# Cap_Drop_LDR.net
KiCad netlist of a schematic drawn in EAGLE
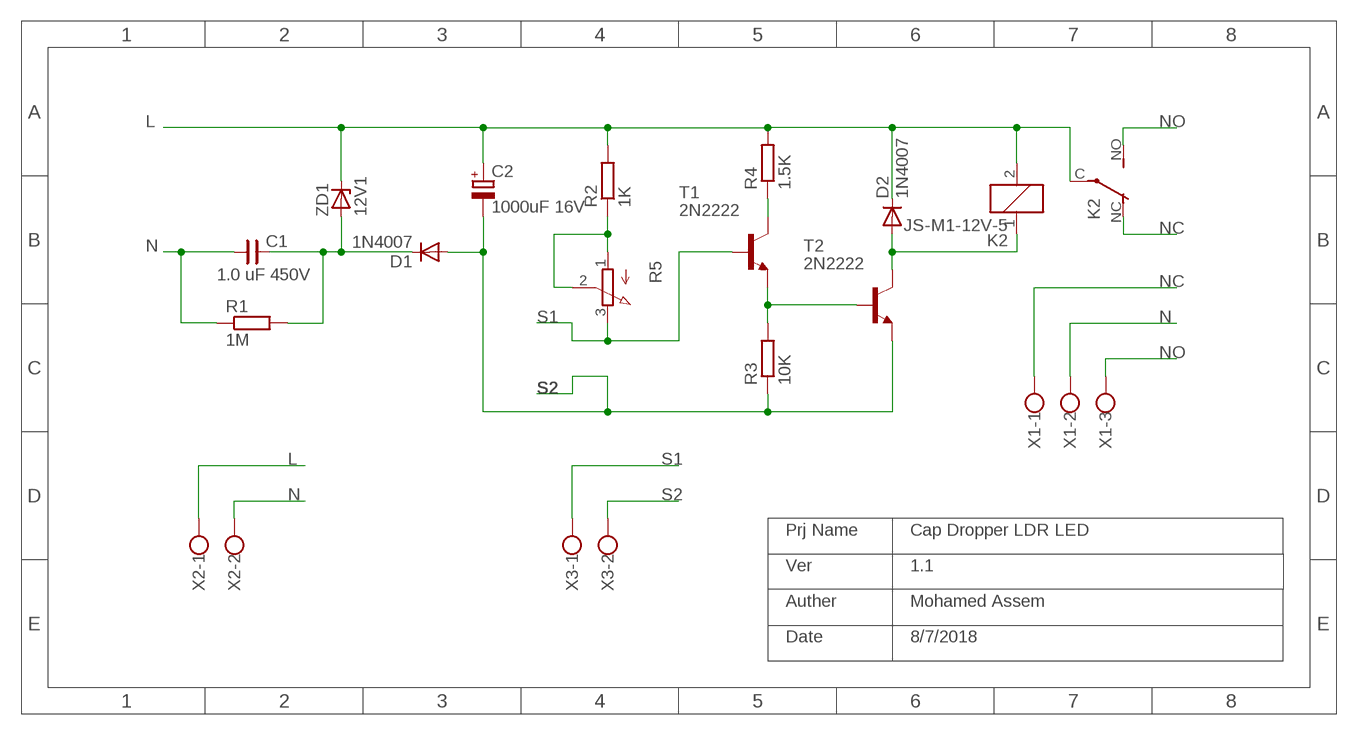
[diagram p0: schematic, sheet 1]

(export (version "E")
  (design (tool "Eeschema 10.0.6"))
  (components
    (comp (ref "C1")
      (value "1.0 uF 450V")
      (footprint "eagle-import:C150-190X070")
      (libsource (lib "eagle-import") (part "CNP-C150-190X070"))
    )
    (comp (ref "C2")
      (value "1000uF 16V")
      (footprint "eagle-import:E5-8,5")
      (libsource (lib "eagle-import") (part "CPOL-EUE5-8.5"))
    )
    (comp (ref "D1")
      (value "1N4007")
      (footprint "eagle-import:DO41-10")
      (libsource (lib "eagle-import") (part "1N4004"))
    )
    (comp (ref "D2")
      (value "1N4007")
      (footprint "eagle-import:DO41-10")
      (libsource (lib "eagle-import") (part "1N4004"))
    )
    (comp (ref "K2")
      (value "JS-M1-12V-5")
      (footprint "eagle-import:JS-M")
      (fields (field (name "MF") "FARNELL") (field (name "MPN") "JSM1-12V-5"))
      (libsource (lib "eagle-import") (part "JS-M1-12V-5"))
    )
    (comp (ref "R1")
      (value "1M")
      (footprint "eagle-import:0207_10")
      (libsource (lib "eagle-import") (part "R-EU_0207/10"))
    )
    (comp (ref "R2")
      (value "1K")
      (footprint "eagle-import:0207_10")
      (libsource (lib "eagle-import") (part "R-EU_0207/10"))
    )
    (comp (ref "R3")
      (value "10K")
      (footprint "eagle-import:0207_10")
      (libsource (lib "eagle-import") (part "R-EU_0207/10"))
    )
    (comp (ref "R4")
      (value "1.5K")
      (footprint "eagle-import:0207_10")
      (libsource (lib "eagle-import") (part "R-EU_0207/10"))
    )
    (comp (ref "R5")
      (value "3RP/1610N")
      (footprint "eagle-import:3RP_1610N")
      (libsource (lib "eagle-import") (part "3RP/1610N"))
    )
    (comp (ref "T1")
      (value "2N2222")
      (footprint "eagle-import:TO92-EBC-OVAL")
      (libsource (lib "eagle-import") (part "2N2222"))
    )
    (comp (ref "T2")
      (value "2N2222")
      (footprint "eagle-import:TO92-EBC-OVAL")
      (libsource (lib "eagle-import") (part "2N2222"))
    )
    (comp (ref "X1")
      (value "W237-103")
      (footprint "eagle-import:W237-103")
      (libsource (lib "eagle-import") (part "W237-103"))
    )
    (comp (ref "X2")
      (value "W237-102")
      (footprint "eagle-import:W237-102")
      (libsource (lib "eagle-import") (part "W237-102"))
    )
    (comp (ref "X3")
      (value "W237-102")
      (footprint "eagle-import:W237-102")
      (libsource (lib "eagle-import") (part "W237-102"))
    )
    (comp (ref "ZD1")
      (value "12V1")
      (footprint "eagle-import:DO35Z10")
      (libsource (lib "eagle-import") (part "ZD-DO35Z10"))
    )
  )
  (nets
    (net (code "1") (name "/L") (class "Default")
      (node (ref "C2") (pin "+") (pinfunction "+_+") (pintype "passive"))
      (node (ref "D2") (pin "C") (pinfunction "C_C") (pintype "passive"))
      (node (ref "K2") (pin "2") (pinfunction "2_2") (pintype "passive"))
      (node (ref "K2") (pin "C") (pinfunction "P_C") (pintype "passive"))
      (node (ref "R2") (pin "2") (pinfunction "2_2") (pintype "passive"))
      (node (ref "R4") (pin "2") (pinfunction "2_2") (pintype "passive"))
      (node (ref "X2") (pin "1") (pinfunction "KL_1") (pintype "passive"))
      (node (ref "ZD1") (pin "C") (pinfunction "C_C") (pintype "passive"))
    )
    (net (code "2") (name "/N") (class "Default")
      (node (ref "C1") (pin "1") (pinfunction "1_1") (pintype "passive"))
      (node (ref "R1") (pin "1") (pinfunction "1_1") (pintype "passive"))
      (node (ref "X1") (pin "2") (pinfunction "KL_2") (pintype "passive"))
      (node (ref "X2") (pin "2") (pinfunction "KL_2") (pintype "passive"))
    )
    (net (code "3") (name "/NC") (class "Default")
      (node (ref "K2") (pin "NC") (pinfunction "O_NC") (pintype "passive"))
      (node (ref "X1") (pin "1") (pinfunction "KL_1") (pintype "passive"))
    )
    (net (code "4") (name "/NO") (class "Default")
      (node (ref "K2") (pin "NO") (pinfunction "S_NO") (pintype "passive"))
      (node (ref "X1") (pin "3") (pinfunction "KL_3") (pintype "passive"))
    )
    (net (code "5") (name "/S1") (class "Default")
      (node (ref "R5") (pin "3") (pinfunction "E_3") (pintype "passive"))
      (node (ref "T1") (pin "B") (pinfunction "B_B") (pintype "passive"))
      (node (ref "X3") (pin "1") (pinfunction "KL_1") (pintype "passive"))
    )
    (net (code "6") (name "/S2") (class "Default")
      (node (ref "C2") (pin "-") (pinfunction "-_-") (pintype "passive"))
      (node (ref "D1") (pin "A") (pinfunction "A_A") (pintype "passive"))
      (node (ref "R3") (pin "1") (pinfunction "1_1") (pintype "passive"))
      (node (ref "T2") (pin "E") (pinfunction "E_E") (pintype "passive"))
      (node (ref "X3") (pin "2") (pinfunction "KL_2") (pintype "passive"))
    )
    (net (code "7") (name "Net-(C1-Pad2)") (class "Default")
      (node (ref "C1") (pin "2") (pinfunction "2_2") (pintype "passive"))
      (node (ref "D1") (pin "C") (pinfunction "C_C") (pintype "passive"))
      (node (ref "R1") (pin "2") (pinfunction "2_2") (pintype "passive"))
      (node (ref "ZD1") (pin "A") (pinfunction "A_A") (pintype "passive"))
    )
    (net (code "8") (name "Net-(D2-PadA)") (class "Default")
      (node (ref "D2") (pin "A") (pinfunction "A_A") (pintype "passive"))
      (node (ref "K2") (pin "1") (pinfunction "1_1") (pintype "passive"))
      (node (ref "T2") (pin "C") (pinfunction "C_C") (pintype "passive"))
    )
    (net (code "9") (name "Net-(R3-Pad2)") (class "Default")
      (node (ref "R3") (pin "2") (pinfunction "2_2") (pintype "passive"))
      (node (ref "T1") (pin "E") (pinfunction "E_E") (pintype "passive"))
      (node (ref "T2") (pin "B") (pinfunction "B_B") (pintype "passive"))
    )
    (net (code "10") (name "Net-(R4-Pad1)") (class "Default")
      (node (ref "R4") (pin "1") (pinfunction "1_1") (pintype "passive"))
      (node (ref "T1") (pin "C") (pinfunction "C_C") (pintype "passive"))
    )
    (net (code "11") (name "Net-(R5-A)") (class "Default")
      (node (ref "R2") (pin "1") (pinfunction "1_1") (pintype "passive"))
      (node (ref "R5") (pin "1") (pinfunction "A_1") (pintype "passive"))
      (node (ref "R5") (pin "2") (pinfunction "S_2") (pintype "passive"))
    )
  )
)
